# DDS_channel.net
KiCad netlist of a schematic drawn in Altium Designer
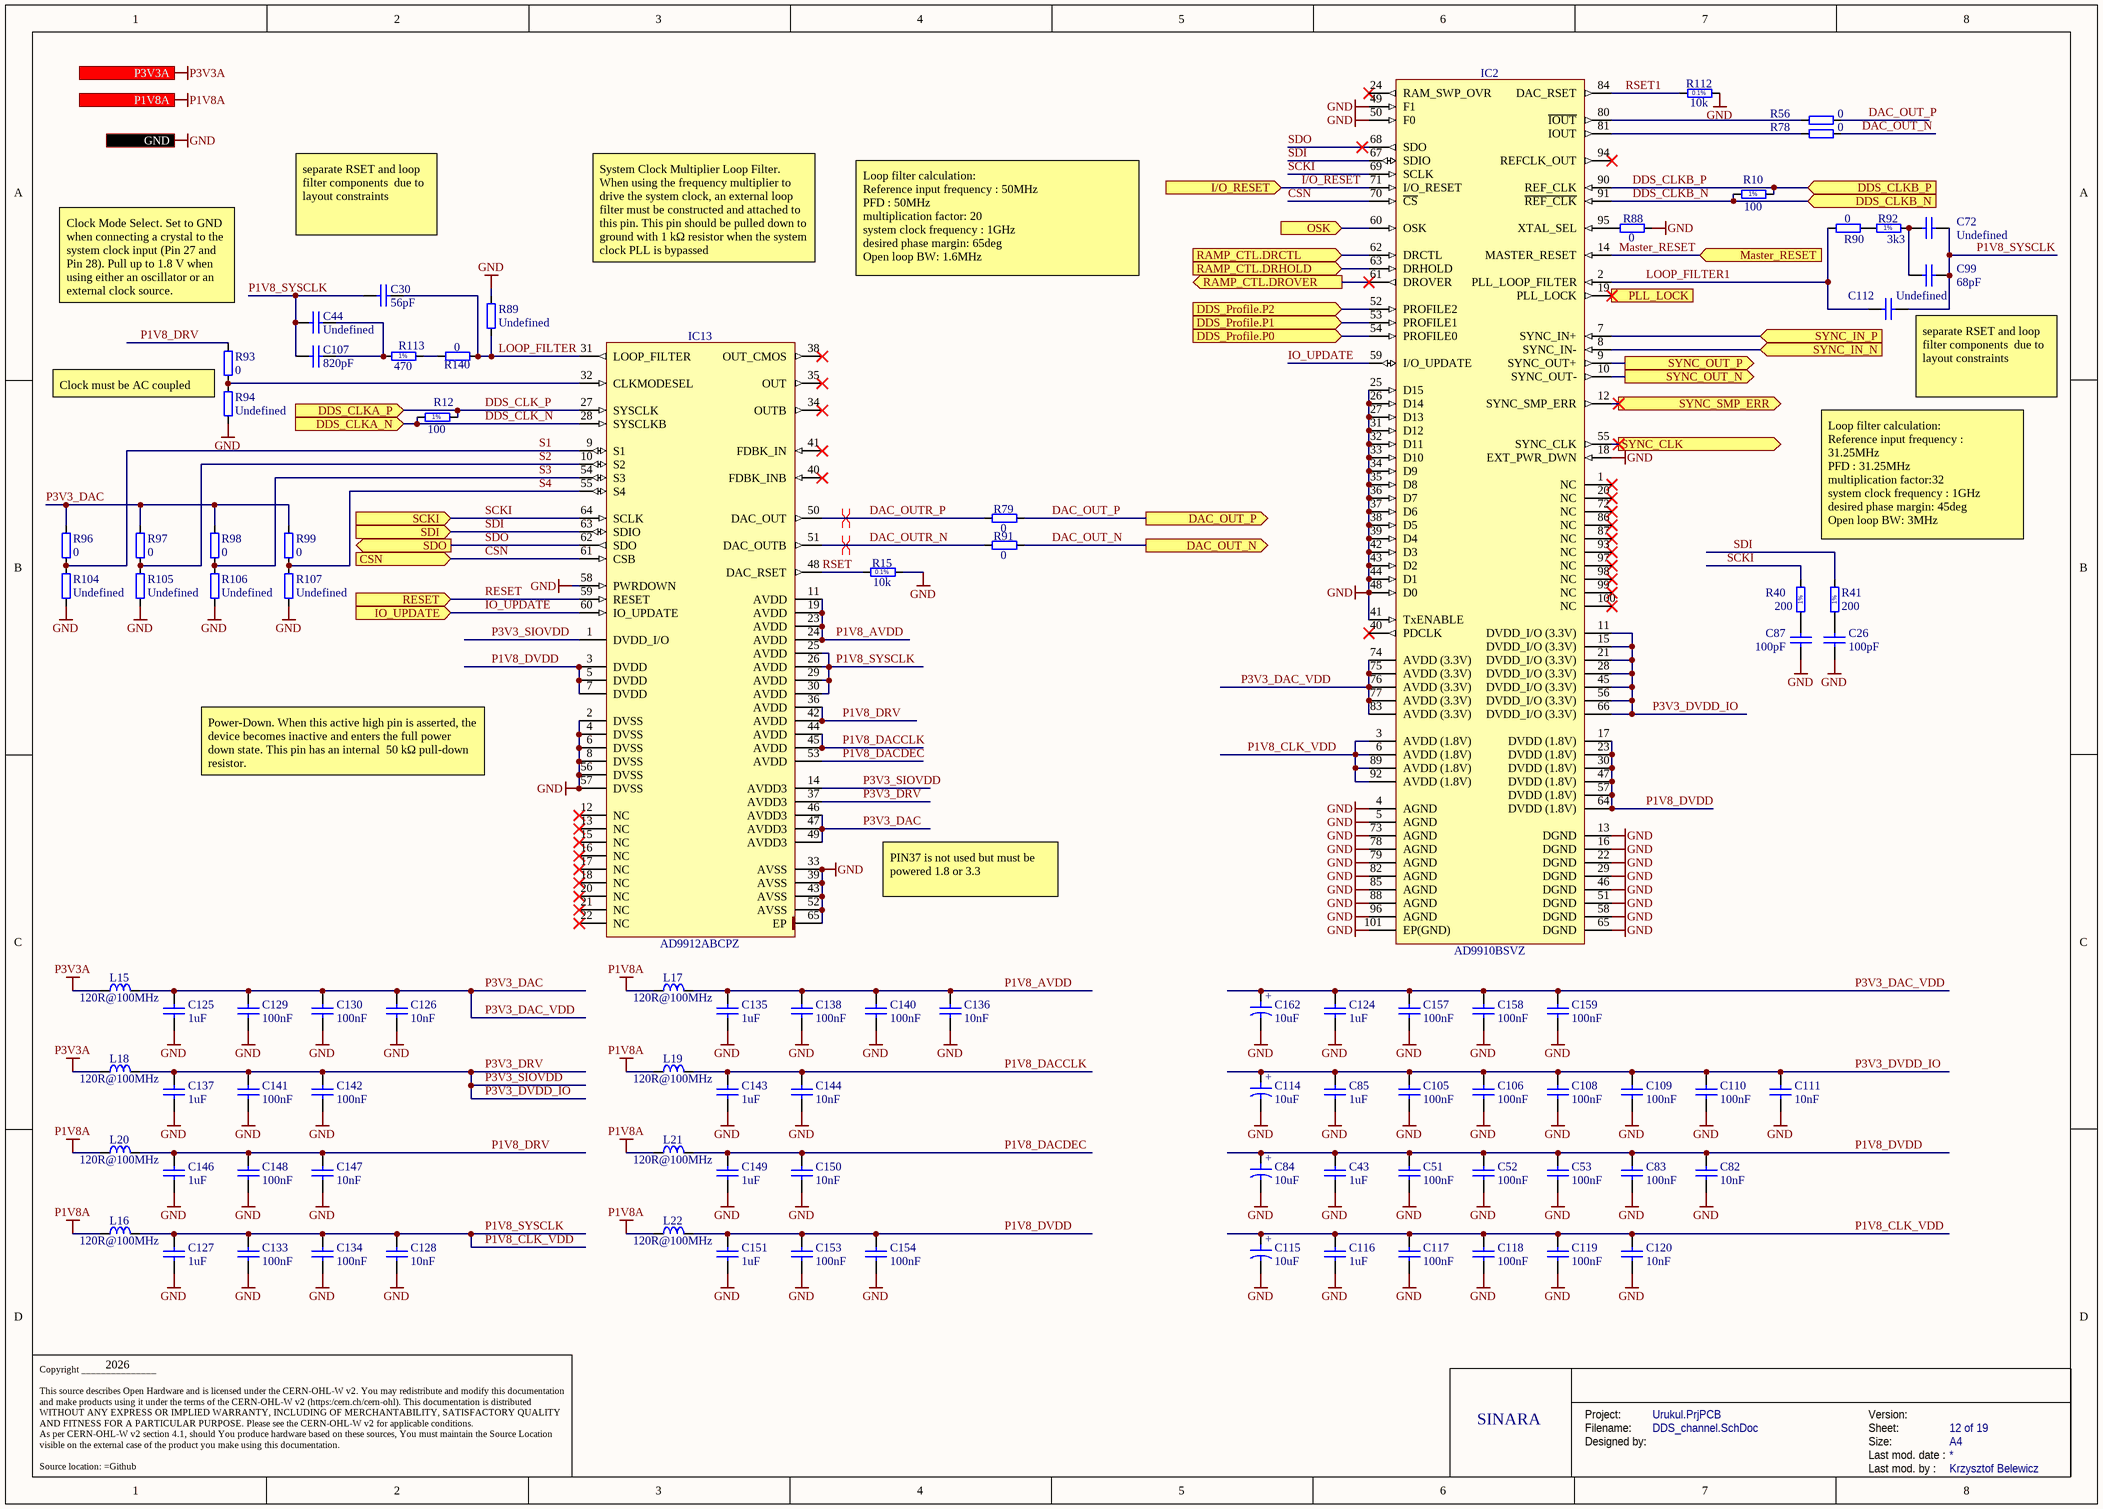
[diagram p0: DDS_channel.SchDoc]

(export (version "E")
  (design (tool "Eeschema 10.0.6"))
  (components
    (comp (ref "C26")
      (value "100pF")
      (footprint "CAPC1005X55N")
      (description "Non-polarised capacitor")
      (fields
        (field (name "PART NUMBER") "CC0402_100PF_50V_5%_C0G")
        (field (name "VOLTAGE") "50V")
        (field (name "AUTHOR") "CERN DEM JLC")
      )
      (libsource (lib "Capacitors") (part "Capacitor - non polarized"))
    )
    (comp (ref "C30")
      (value "56pF")
      (footprint "CAPC1608X87N")
      (description "Non-polarised capacitor")
      (fields
        (field (name "PART NUMBER") "CC0603_56PF_50V_5%_NP0")
        (field (name "VOLTAGE") "50V")
        (field (name "AUTHOR") "CERN DEM JLC")
      )
      (libsource (lib "Capacitors") (part "Capacitor - non polarized"))
    )
    (comp (ref "C43")
      (value "1uF")
      (footprint "CAPC1005X55N")
      (description "Non-polarised capacitor")
      (fields
        (field (name "PART NUMBER") "CC0402_1UF_16V_10%_X5R")
        (field (name "VOLTAGE") "16V")
        (field (name "AUTHOR") "CERN DEM JLC")
      )
      (libsource (lib "Capacitors") (part "Capacitor - non polarized"))
    )
    (comp (ref "C44")
      (value "Undefined")
      (footprint "CAPC1608X90N")
      (description "Non-polarised capacitor")
      (fields (field (name "PART NUMBER") "CC0603_NO-VALUE") (field (name "AUTHOR") "CERN DEM MR"))
      (libsource (lib "Capacitors") (part "Capacitor - non polarized"))
    )
    (comp (ref "C51")
      (value "100nF")
      (footprint "CAPC1005X55N")
      (description "Non-polarised capacitor")
      (fields
        (field (name "PART NUMBER") "CC0402_100NF_16V_10%_X5R")
        (field (name "VOLTAGE") "16V")
        (field (name "AUTHOR") "CERN DEM JLC")
      )
      (libsource (lib "Capacitors") (part "Capacitor - non polarized"))
    )
    (comp (ref "C52")
      (value "100nF")
      (footprint "CAPC1005X55N")
      (description "Non-polarised capacitor")
      (fields
        (field (name "PART NUMBER") "CC0402_100NF_16V_10%_X5R")
        (field (name "VOLTAGE") "16V")
        (field (name "AUTHOR") "CERN DEM JLC")
      )
      (libsource (lib "Capacitors") (part "Capacitor - non polarized"))
    )
    (comp (ref "C53")
      (value "100nF")
      (footprint "CAPC1005X55N")
      (description "Non-polarised capacitor")
      (fields
        (field (name "PART NUMBER") "CC0402_100NF_16V_10%_X5R")
        (field (name "VOLTAGE") "16V")
        (field (name "AUTHOR") "CERN DEM JLC")
      )
      (libsource (lib "Capacitors") (part "Capacitor - non polarized"))
    )
    (comp (ref "C72")
      (value "Undefined")
      (footprint "CAPC1608X90N")
      (description "Non-polarised capacitor")
      (fields (field (name "PART NUMBER") "CC0603_NO-VALUE") (field (name "AUTHOR") "CERN DEM MR"))
      (libsource (lib "Capacitors") (part "Capacitor - non polarized"))
    )
    (comp (ref "C82")
      (value "10nF")
      (footprint "CAPC1005X55N")
      (description "Non-polarised capacitor")
      (fields
        (field (name "PART NUMBER") "CC0402_10NF_16V_10%_X7R")
        (field (name "VOLTAGE") "16V")
        (field (name "AUTHOR") "CERN DEM JLC")
      )
      (libsource (lib "Capacitors") (part "Capacitor - non polarized"))
    )
    (comp (ref "C83")
      (value "100nF")
      (footprint "CAPC1005X55N")
      (description "Non-polarised capacitor")
      (fields
        (field (name "PART NUMBER") "CC0402_100NF_16V_10%_X5R")
        (field (name "VOLTAGE") "16V")
        (field (name "AUTHOR") "CERN DEM JLC")
      )
      (libsource (lib "Capacitors") (part "Capacitor - non polarized"))
    )
    (comp (ref "C84")
      (value "10uF")
      (footprint "CAPMP6032X280N")
      (description "Polarised capacitor")
      (fields
        (field (name "PART NUMBER") "CTE6032-28_10UF_25V_10%_LESR0500")
        (field (name "VOLTAGE") "25V")
        (field (name "AUTHOR") "CERN DEM JLC")
      )
      (libsource (lib "Capacitors") (part "Capacitor - polarized"))
    )
    (comp (ref "C85")
      (value "1uF")
      (footprint "CAPC1005X55N")
      (description "Non-polarised capacitor")
      (fields
        (field (name "PART NUMBER") "CC0402_1UF_16V_10%_X5R")
        (field (name "VOLTAGE") "16V")
        (field (name "AUTHOR") "CERN DEM JLC")
      )
      (libsource (lib "Capacitors") (part "Capacitor - non polarized"))
    )
    (comp (ref "C87")
      (value "100pF")
      (footprint "CAPC1005X55N")
      (description "Non-polarised capacitor")
      (fields
        (field (name "PART NUMBER") "CC0402_100PF_50V_5%_C0G")
        (field (name "VOLTAGE") "50V")
        (field (name "AUTHOR") "CERN DEM JLC")
      )
      (libsource (lib "Capacitors") (part "Capacitor - non polarized"))
    )
    (comp (ref "C99")
      (value "68pF")
      (footprint "CAPC1608X87N")
      (description "Non-polarised capacitor")
      (fields
        (field (name "PART NUMBER") "CC0603_68PF_50V_5%_NP0")
        (field (name "VOLTAGE") "50V")
        (field (name "AUTHOR") "CERN DEM JLC")
      )
      (libsource (lib "Capacitors") (part "Capacitor - non polarized"))
    )
    (comp (ref "C105")
      (value "100nF")
      (footprint "CAPC1005X55N")
      (description "Non-polarised capacitor")
      (fields
        (field (name "PART NUMBER") "CC0402_100NF_16V_10%_X5R")
        (field (name "VOLTAGE") "16V")
        (field (name "AUTHOR") "CERN DEM JLC")
      )
      (libsource (lib "Capacitors") (part "Capacitor - non polarized"))
    )
    (comp (ref "C106")
      (value "100nF")
      (footprint "CAPC1005X55N")
      (description "Non-polarised capacitor")
      (fields
        (field (name "PART NUMBER") "CC0402_100NF_16V_10%_X5R")
        (field (name "VOLTAGE") "16V")
        (field (name "AUTHOR") "CERN DEM JLC")
      )
      (libsource (lib "Capacitors") (part "Capacitor - non polarized"))
    )
    (comp (ref "C107")
      (value "820pF")
      (footprint "CAPC2012X135N")
      (description "Non-polarised capacitor")
      (fields
        (field (name "PART NUMBER") "CC0805_820PF_50V_5%_NP0")
        (field (name "VOLTAGE") "50V")
        (field (name "AUTHOR") "CERN DEM JLC")
      )
      (libsource (lib "Capacitors") (part "Capacitor - non polarized"))
    )
    (comp (ref "C108")
      (value "100nF")
      (footprint "CAPC1005X55N")
      (description "Non-polarised capacitor")
      (fields
        (field (name "PART NUMBER") "CC0402_100NF_16V_10%_X5R")
        (field (name "VOLTAGE") "16V")
        (field (name "AUTHOR") "CERN DEM JLC")
      )
      (libsource (lib "Capacitors") (part "Capacitor - non polarized"))
    )
    (comp (ref "C109")
      (value "100nF")
      (footprint "CAPC1005X55N")
      (description "Non-polarised capacitor")
      (fields
        (field (name "PART NUMBER") "CC0402_100NF_16V_10%_X5R")
        (field (name "VOLTAGE") "16V")
        (field (name "AUTHOR") "CERN DEM JLC")
      )
      (libsource (lib "Capacitors") (part "Capacitor - non polarized"))
    )
    (comp (ref "C110")
      (value "100nF")
      (footprint "CAPC1005X55N")
      (description "Non-polarised capacitor")
      (fields
        (field (name "PART NUMBER") "CC0402_100NF_16V_10%_X5R")
        (field (name "VOLTAGE") "16V")
        (field (name "AUTHOR") "CERN DEM JLC")
      )
      (libsource (lib "Capacitors") (part "Capacitor - non polarized"))
    )
    (comp (ref "C111")
      (value "10nF")
      (footprint "CAPC1005X55N")
      (description "Non-polarised capacitor")
      (fields
        (field (name "PART NUMBER") "CC0402_10NF_16V_10%_X7R")
        (field (name "VOLTAGE") "16V")
        (field (name "AUTHOR") "CERN DEM JLC")
      )
      (libsource (lib "Capacitors") (part "Capacitor - non polarized"))
    )
    (comp (ref "C112")
      (value "Undefined")
      (footprint "CAPC1608X90N")
      (description "Non-polarised capacitor")
      (fields (field (name "PART NUMBER") "CC0603_NO-VALUE") (field (name "AUTHOR") "CERN DEM MR"))
      (libsource (lib "Capacitors") (part "Capacitor - non polarized"))
    )
    (comp (ref "C114")
      (value "10uF")
      (footprint "CAPMP6032X280N")
      (description "Polarised capacitor")
      (fields
        (field (name "PART NUMBER") "CTE6032-28_10UF_25V_10%_LESR0500")
        (field (name "VOLTAGE") "25V")
        (field (name "AUTHOR") "CERN DEM JLC")
      )
      (libsource (lib "Capacitors") (part "Capacitor - polarized"))
    )
    (comp (ref "C115")
      (value "10uF")
      (footprint "CAPMP6032X280N")
      (description "Polarised capacitor")
      (fields
        (field (name "PART NUMBER") "CTE6032-28_10UF_25V_10%_LESR0500")
        (field (name "VOLTAGE") "25V")
        (field (name "AUTHOR") "CERN DEM JLC")
      )
      (libsource (lib "Capacitors") (part "Capacitor - polarized"))
    )
    (comp (ref "C116")
      (value "1uF")
      (footprint "CAPC1005X55N")
      (description "Non-polarised capacitor")
      (fields
        (field (name "PART NUMBER") "CC0402_1UF_16V_10%_X5R")
        (field (name "VOLTAGE") "16V")
        (field (name "AUTHOR") "CERN DEM JLC")
      )
      (libsource (lib "Capacitors") (part "Capacitor - non polarized"))
    )
    (comp (ref "C117")
      (value "100nF")
      (footprint "CAPC1005X55N")
      (description "Non-polarised capacitor")
      (fields
        (field (name "PART NUMBER") "CC0402_100NF_16V_10%_X5R")
        (field (name "VOLTAGE") "16V")
        (field (name "AUTHOR") "CERN DEM JLC")
      )
      (libsource (lib "Capacitors") (part "Capacitor - non polarized"))
    )
    (comp (ref "C118")
      (value "100nF")
      (footprint "CAPC1005X55N")
      (description "Non-polarised capacitor")
      (fields
        (field (name "PART NUMBER") "CC0402_100NF_16V_10%_X5R")
        (field (name "VOLTAGE") "16V")
        (field (name "AUTHOR") "CERN DEM JLC")
      )
      (libsource (lib "Capacitors") (part "Capacitor - non polarized"))
    )
    (comp (ref "C119")
      (value "100nF")
      (footprint "CAPC1005X55N")
      (description "Non-polarised capacitor")
      (fields
        (field (name "PART NUMBER") "CC0402_100NF_16V_10%_X5R")
        (field (name "VOLTAGE") "16V")
        (field (name "AUTHOR") "CERN DEM JLC")
      )
      (libsource (lib "Capacitors") (part "Capacitor - non polarized"))
    )
    (comp (ref "C120")
      (value "10nF")
      (footprint "CAPC1005X55N")
      (description "Non-polarised capacitor")
      (fields
        (field (name "PART NUMBER") "CC0402_10NF_16V_10%_X7R")
        (field (name "VOLTAGE") "16V")
        (field (name "AUTHOR") "CERN DEM JLC")
      )
      (libsource (lib "Capacitors") (part "Capacitor - non polarized"))
    )
    (comp (ref "C124")
      (value "1uF")
      (footprint "CAPC1005X55N")
      (description "Non-polarised capacitor")
      (fields
        (field (name "PART NUMBER") "CC0402_1UF_16V_10%_X5R")
        (field (name "VOLTAGE") "16V")
        (field (name "AUTHOR") "CERN DEM JLC")
      )
      (libsource (lib "Capacitors") (part "Capacitor - non polarized"))
    )
    (comp (ref "C125")
      (value "1uF")
      (footprint "CAPC1005X55N")
      (description "Non-polarised capacitor")
      (fields
        (field (name "PART NUMBER") "CC0402_1UF_16V_10%_X5R")
        (field (name "VOLTAGE") "16V")
        (field (name "AUTHOR") "CERN DEM JLC")
      )
      (libsource (lib "Capacitors") (part "Capacitor - non polarized"))
    )
    (comp (ref "C126")
      (value "10nF")
      (footprint "CAPC1005X55N")
      (description "Non-polarised capacitor")
      (fields
        (field (name "PART NUMBER") "CC0402_10NF_16V_10%_X7R")
        (field (name "VOLTAGE") "16V")
        (field (name "AUTHOR") "CERN DEM JLC")
      )
      (libsource (lib "Capacitors") (part "Capacitor - non polarized"))
    )
    (comp (ref "C127")
      (value "1uF")
      (footprint "CAPC1005X55N")
      (description "Non-polarised capacitor")
      (fields
        (field (name "PART NUMBER") "CC0402_1UF_16V_10%_X5R")
        (field (name "VOLTAGE") "16V")
        (field (name "AUTHOR") "CERN DEM JLC")
      )
      (libsource (lib "Capacitors") (part "Capacitor - non polarized"))
    )
    (comp (ref "C128")
      (value "10nF")
      (footprint "CAPC1005X55N")
      (description "Non-polarised capacitor")
      (fields
        (field (name "PART NUMBER") "CC0402_10NF_16V_10%_X7R")
        (field (name "VOLTAGE") "16V")
        (field (name "AUTHOR") "CERN DEM JLC")
      )
      (libsource (lib "Capacitors") (part "Capacitor - non polarized"))
    )
    (comp (ref "C129")
      (value "100nF")
      (footprint "CAPC1005X55N")
      (description "Non-polarised capacitor")
      (fields
        (field (name "PART NUMBER") "CC0402_100NF_16V_10%_X5R")
        (field (name "VOLTAGE") "16V")
        (field (name "AUTHOR") "CERN DEM JLC")
      )
      (libsource (lib "Capacitors") (part "Capacitor - non polarized"))
    )
    (comp (ref "C130")
      (value "100nF")
      (footprint "CAPC1005X55N")
      (description "Non-polarised capacitor")
      (fields
        (field (name "PART NUMBER") "CC0402_100NF_16V_10%_X5R")
        (field (name "VOLTAGE") "16V")
        (field (name "AUTHOR") "CERN DEM JLC")
      )
      (libsource (lib "Capacitors") (part "Capacitor - non polarized"))
    )
    (comp (ref "C133")
      (value "100nF")
      (footprint "CAPC1005X55N")
      (description "Non-polarised capacitor")
      (fields
        (field (name "PART NUMBER") "CC0402_100NF_16V_10%_X5R")
        (field (name "VOLTAGE") "16V")
        (field (name "AUTHOR") "CERN DEM JLC")
      )
      (libsource (lib "Capacitors") (part "Capacitor - non polarized"))
    )
    (comp (ref "C134")
      (value "100nF")
      (footprint "CAPC1005X55N")
      (description "Non-polarised capacitor")
      (fields
        (field (name "PART NUMBER") "CC0402_100NF_16V_10%_X5R")
        (field (name "VOLTAGE") "16V")
        (field (name "AUTHOR") "CERN DEM JLC")
      )
      (libsource (lib "Capacitors") (part "Capacitor - non polarized"))
    )
    (comp (ref "C135")
      (value "1uF")
      (footprint "CAPC1005X55N")
      (description "Non-polarised capacitor")
      (fields
        (field (name "PART NUMBER") "CC0402_1UF_16V_10%_X5R")
        (field (name "VOLTAGE") "16V")
        (field (name "AUTHOR") "CERN DEM JLC")
      )
      (libsource (lib "Capacitors") (part "Capacitor - non polarized"))
    )
    (comp (ref "C136")
      (value "10nF")
      (footprint "CAPC1005X55N")
      (description "Non-polarised capacitor")
      (fields
        (field (name "PART NUMBER") "CC0402_10NF_16V_10%_X7R")
        (field (name "VOLTAGE") "16V")
        (field (name "AUTHOR") "CERN DEM JLC")
      )
      (libsource (lib "Capacitors") (part "Capacitor - non polarized"))
    )
    (comp (ref "C137")
      (value "1uF")
      (footprint "CAPC1005X55N")
      (description "Non-polarised capacitor")
      (fields
        (field (name "PART NUMBER") "CC0402_1UF_16V_10%_X5R")
        (field (name "VOLTAGE") "16V")
        (field (name "AUTHOR") "CERN DEM JLC")
      )
      (libsource (lib "Capacitors") (part "Capacitor - non polarized"))
    )
    (comp (ref "C138")
      (value "100nF")
      (footprint "CAPC1005X55N")
      (description "Non-polarised capacitor")
      (fields
        (field (name "PART NUMBER") "CC0402_100NF_16V_10%_X5R")
        (field (name "VOLTAGE") "16V")
        (field (name "AUTHOR") "CERN DEM JLC")
      )
      (libsource (lib "Capacitors") (part "Capacitor - non polarized"))
    )
    (comp (ref "C140")
      (value "100nF")
      (footprint "CAPC1005X55N")
      (description "Non-polarised capacitor")
      (fields
        (field (name "PART NUMBER") "CC0402_100NF_16V_10%_X5R")
        (field (name "VOLTAGE") "16V")
        (field (name "AUTHOR") "CERN DEM JLC")
      )
      (libsource (lib "Capacitors") (part "Capacitor - non polarized"))
    )
    (comp (ref "C141")
      (value "100nF")
      (footprint "CAPC1005X55N")
      (description "Non-polarised capacitor")
      (fields
        (field (name "PART NUMBER") "CC0402_100NF_16V_10%_X5R")
        (field (name "VOLTAGE") "16V")
        (field (name "AUTHOR") "CERN DEM JLC")
      )
      (libsource (lib "Capacitors") (part "Capacitor - non polarized"))
    )
    (comp (ref "C142")
      (value "100nF")
      (footprint "CAPC1005X55N")
      (description "Non-polarised capacitor")
      (fields
        (field (name "PART NUMBER") "CC0402_100NF_16V_10%_X5R")
        (field (name "VOLTAGE") "16V")
        (field (name "AUTHOR") "CERN DEM JLC")
      )
      (libsource (lib "Capacitors") (part "Capacitor - non polarized"))
    )
    (comp (ref "C143")
      (value "1uF")
      (footprint "CAPC1005X55N")
      (description "Non-polarised capacitor")
      (fields
        (field (name "PART NUMBER") "CC0402_1UF_16V_10%_X5R")
        (field (name "VOLTAGE") "16V")
        (field (name "AUTHOR") "CERN DEM JLC")
      )
      (libsource (lib "Capacitors") (part "Capacitor - non polarized"))
    )
    (comp (ref "C144")
      (value "10nF")
      (footprint "CAPC1005X55N")
      (description "Non-polarised capacitor")
      (fields
        (field (name "PART NUMBER") "CC0402_10NF_16V_10%_X7R")
        (field (name "VOLTAGE") "16V")
        (field (name "AUTHOR") "CERN DEM JLC")
      )
      (libsource (lib "Capacitors") (part "Capacitor - non polarized"))
    )
    (comp (ref "C146")
      (value "1uF")
      (footprint "CAPC1005X55N")
      (description "Non-polarised capacitor")
      (fields
        (field (name "PART NUMBER") "CC0402_1UF_16V_10%_X5R")
        (field (name "VOLTAGE") "16V")
        (field (name "AUTHOR") "CERN DEM JLC")
      )
      (libsource (lib "Capacitors") (part "Capacitor - non polarized"))
    )
    (comp (ref "C147")
      (value "10nF")
      (footprint "CAPC1005X55N")
      (description "Non-polarised capacitor")
      (fields
        (field (name "PART NUMBER") "CC0402_10NF_16V_10%_X7R")
        (field (name "VOLTAGE") "16V")
        (field (name "AUTHOR") "CERN DEM JLC")
      )
      (libsource (lib "Capacitors") (part "Capacitor - non polarized"))
    )
    (comp (ref "C148")
      (value "100nF")
      (footprint "CAPC1005X55N")
      (description "Non-polarised capacitor")
      (fields
        (field (name "PART NUMBER") "CC0402_100NF_16V_10%_X5R")
        (field (name "VOLTAGE") "16V")
        (field (name "AUTHOR") "CERN DEM JLC")
      )
      (libsource (lib "Capacitors") (part "Capacitor - non polarized"))
    )
    (comp (ref "C149")
      (value "1uF")
      (footprint "CAPC1005X55N")
      (description "Non-polarised capacitor")
      (fields
        (field (name "PART NUMBER") "CC0402_1UF_16V_10%_X5R")
        (field (name "VOLTAGE") "16V")
        (field (name "AUTHOR") "CERN DEM JLC")
      )
      (libsource (lib "Capacitors") (part "Capacitor - non polarized"))
    )
    (comp (ref "C150")
      (value "10nF")
      (footprint "CAPC1005X55N")
      (description "Non-polarised capacitor")
      (fields
        (field (name "PART NUMBER") "CC0402_10NF_16V_10%_X7R")
        (field (name "VOLTAGE") "16V")
        (field (name "AUTHOR") "CERN DEM JLC")
      )
      (libsource (lib "Capacitors") (part "Capacitor - non polarized"))
    )
    (comp (ref "C151")
      (value "1uF")
      (footprint "CAPC1005X55N")
      (description "Non-polarised capacitor")
      (fields
        (field (name "PART NUMBER") "CC0402_1UF_16V_10%_X5R")
        (field (name "VOLTAGE") "16V")
        (field (name "AUTHOR") "CERN DEM JLC")
      )
      (libsource (lib "Capacitors") (part "Capacitor - non polarized"))
    )
    (comp (ref "C153")
      (value "100nF")
      (footprint "CAPC1005X55N")
      (description "Non-polarised capacitor")
      (fields
        (field (name "PART NUMBER") "CC0402_100NF_16V_10%_X5R")
        (field (name "VOLTAGE") "16V")
        (field (name "AUTHOR") "CERN DEM JLC")
      )
      (libsource (lib "Capacitors") (part "Capacitor - non polarized"))
    )
    (comp (ref "C154")
      (value "100nF")
      (footprint "CAPC1005X55N")
      (description "Non-polarised capacitor")
      (fields
        (field (name "PART NUMBER") "CC0402_100NF_16V_10%_X5R")
        (field (name "VOLTAGE") "16V")
        (field (name "AUTHOR") "CERN DEM JLC")
      )
      (libsource (lib "Capacitors") (part "Capacitor - non polarized"))
    )
    (comp (ref "C157")
      (value "100nF")
      (footprint "CAPC1005X55N")
      (description "Non-polarised capacitor")
      (fields
        (field (name "PART NUMBER") "CC0402_100NF_16V_10%_X5R")
        (field (name "VOLTAGE") "16V")
        (field (name "AUTHOR") "CERN DEM JLC")
      )
      (libsource (lib "Capacitors") (part "Capacitor - non polarized"))
    )
    (comp (ref "C158")
      (value "100nF")
      (footprint "CAPC1005X55N")
      (description "Non-polarised capacitor")
      (fields
        (field (name "PART NUMBER") "CC0402_100NF_16V_10%_X5R")
        (field (name "VOLTAGE") "16V")
        (field (name "AUTHOR") "CERN DEM JLC")
      )
      (libsource (lib "Capacitors") (part "Capacitor - non polarized"))
    )
    (comp (ref "C159")
      (value "100nF")
      (footprint "CAPC1005X55N")
      (description "Non-polarised capacitor")
      (fields
        (field (name "PART NUMBER") "CC0402_100NF_16V_10%_X5R")
        (field (name "VOLTAGE") "16V")
        (field (name "AUTHOR") "CERN DEM JLC")
      )
      (libsource (lib "Capacitors") (part "Capacitor - non polarized"))
    )
    (comp (ref "C162")
      (value "10uF")
      (footprint "CAPMP6032X280N")
      (description "Polarised capacitor")
      (fields
        (field (name "PART NUMBER") "CTE6032-28_10UF_25V_10%_LESR0500")
        (field (name "VOLTAGE") "25V")
        (field (name "AUTHOR") "CERN DEM JLC")
      )
      (libsource (lib "Capacitors") (part "Capacitor - polarized"))
    )
    (comp (ref "IC2")
      (value "AD9910BSVZ")
      (footprint "QFP50P1600X1600X120-101N-S500")
      (description "1 GSPS, 14-Bit, 3.3 V CMOS Direct Digital Synthesizer")
      (fields (field (name "MANUFACTURER") "ANALOG DEVICES") (field (name "AUTHOR") "CERN DEM JLC"))
      (libsource (lib "ICs And Semiconductors") (part "AD9910"))
    )
    (comp (ref "IC13")
      (value "AD9912ABCPZ")
      (footprint "QFN50P900X900X100-65N-S536")
      (description "1 GSPS Direct Digital Synthetizer with 14-Bit DAC")
      (fields (field (name "MANUFACTURER") "ANALOG DEVICES") (field (name "AUTHOR") "CERN DEM JLC"))
      (libsource (lib "ICs And Semiconductors") (part "AD9912"))
    )
    (comp (ref "L15")
      (value "120R@100MHz")
      (footprint "INDC1608X95N")
      (description "Inductor")
      (fields
        (field (name "PART NUMBER") "IND0603_MURATA_BLM18PG121SN1D")
        (field (name "POWER") "2A")
        (field (name "AUTHOR") "CERN DEM BC")
      )
      (libsource (lib "Inductors & Transformers") (part "Inductor"))
    )
    (comp (ref "L16")
      (value "120R@100MHz")
      (footprint "INDC1608X95N")
      (description "Inductor")
      (fields
        (field (name "PART NUMBER") "IND0603_MURATA_BLM18PG121SN1D")
        (field (name "POWER") "2A")
        (field (name "AUTHOR") "CERN DEM BC")
      )
      (libsource (lib "Inductors & Transformers") (part "Inductor"))
    )
    (comp (ref "L17")
      (value "120R@100MHz")
      (footprint "INDC1608X95N")
      (description "Inductor")
      (fields
        (field (name "PART NUMBER") "IND0603_MURATA_BLM18PG121SN1D")
        (field (name "POWER") "2A")
        (field (name "AUTHOR") "CERN DEM BC")
      )
      (libsource (lib "Inductors & Transformers") (part "Inductor"))
    )
    (comp (ref "L18")
      (value "120R@100MHz")
      (footprint "INDC1608X95N")
      (description "Inductor")
      (fields
        (field (name "PART NUMBER") "IND0603_MURATA_BLM18PG121SN1D")
        (field (name "POWER") "2A")
        (field (name "AUTHOR") "CERN DEM BC")
      )
      (libsource (lib "Inductors & Transformers") (part "Inductor"))
    )
    (comp (ref "L19")
      (value "120R@100MHz")
      (footprint "INDC1608X95N")
      (description "Inductor")
      (fields
        (field (name "PART NUMBER") "IND0603_MURATA_BLM18PG121SN1D")
        (field (name "POWER") "2A")
        (field (name "AUTHOR") "CERN DEM BC")
      )
      (libsource (lib "Inductors & Transformers") (part "Inductor"))
    )
    (comp (ref "L20")
      (value "120R@100MHz")
      (footprint "INDC1608X95N")
      (description "Inductor")
      (fields
        (field (name "PART NUMBER") "IND0603_MURATA_BLM18PG121SN1D")
        (field (name "POWER") "2A")
        (field (name "AUTHOR") "CERN DEM BC")
      )
      (libsource (lib "Inductors & Transformers") (part "Inductor"))
    )
    (comp (ref "L21")
      (value "120R@100MHz")
      (footprint "INDC1608X95N")
      (description "Inductor")
      (fields
        (field (name "PART NUMBER") "IND0603_MURATA_BLM18PG121SN1D")
        (field (name "POWER") "2A")
        (field (name "AUTHOR") "CERN DEM BC")
      )
      (libsource (lib "Inductors & Transformers") (part "Inductor"))
    )
    (comp (ref "L22")
      (value "120R@100MHz")
      (footprint "INDC1608X95N")
      (description "Inductor")
      (fields
        (field (name "PART NUMBER") "IND0603_MURATA_BLM18PG121SN1D")
        (field (name "POWER") "2A")
        (field (name "AUTHOR") "CERN DEM BC")
      )
      (libsource (lib "Inductors & Transformers") (part "Inductor"))
    )
    (comp (ref "R10")
      (value "100")
      (footprint "RESC1005X40N")
      (description "Resistor - 1%")
      (fields
        (field (name "PART NUMBER") "R0402_100R_1%_0.0625W_100PPM")
        (field (name "POWER") "0.0625W")
        (field (name "AUTHOR") "CERN DEM JLC")
      )
      (libsource (lib "Resistors") (part "Resistor - 1%"))
    )
    (comp (ref "R12")
      (value "100")
      (footprint "RESC1005X40N")
      (description "Resistor - 1%")
      (fields
        (field (name "PART NUMBER") "R0402_100R_1%_0.0625W_100PPM")
        (field (name "POWER") "0.0625W")
        (field (name "AUTHOR") "CERN DEM JLC")
      )
      (libsource (lib "Resistors") (part "Resistor - 1%"))
    )
    (comp (ref "R15")
      (value "10k")
      (footprint "RESC1005X35N")
      (description "Resistor - 0.1%")
      (fields
        (field (name "PART NUMBER") "R0402_10K_0.1%_0.063W_25PPM")
        (field (name "POWER") "0.063W")
        (field (name "AUTHOR") "CERN DEM JMW")
      )
      (libsource (lib "Resistors") (part "Resistor - 0.1%"))
    )
    (comp (ref "R40")
      (value "200")
      (footprint "RESC1005X40N")
      (description "Resistor - 1%")
      (fields
        (field (name "PART NUMBER") "R0402_200R_1%_0.0625W_100PPM")
        (field (name "POWER") "0.0625W")
        (field (name "AUTHOR") "CERN DEM JLC")
      )
      (libsource (lib "Resistors") (part "Resistor - 1%"))
    )
    (comp (ref "R41")
      (value "200")
      (footprint "RESC1005X40N")
      (description "Resistor - 1%")
      (fields
        (field (name "PART NUMBER") "R0402_200R_1%_0.0625W_100PPM")
        (field (name "POWER") "0.0625W")
        (field (name "AUTHOR") "CERN DEM JLC")
      )
      (libsource (lib "Resistors") (part "Resistor - 1%"))
    )
    (comp (ref "R56")
      (value "0")
      (footprint "RESC1005X40N")
      (description "Resistor")
      (fields
        (field (name "PART NUMBER") "R0402_0R_JUMPER")
        (field (name "MANUFACTURER") "GENERIC")
        (field (name "AUTHOR") "CERN DEM JLC")
      )
      (libsource (lib "Resistors") (part "Resistor"))
    )
    (comp (ref "R78")
      (value "0")
      (footprint "RESC1005X40N")
      (description "Resistor")
      (fields
        (field (name "PART NUMBER") "R0402_0R_JUMPER")
        (field (name "MANUFACTURER") "GENERIC")
        (field (name "AUTHOR") "CERN DEM JLC")
      )
      (libsource (lib "Resistors") (part "Resistor"))
    )
    (comp (ref "R79")
      (value "0")
      (footprint "RESC1005X40N")
      (description "Resistor")
      (fields
        (field (name "PART NUMBER") "R0402_0R_JUMPER")
        (field (name "MANUFACTURER") "GENERIC")
        (field (name "AUTHOR") "CERN DEM JLC")
      )
      (libsource (lib "Resistors") (part "Resistor"))
    )
    (comp (ref "R88")
      (value "0")
      (footprint "RESC1005X40N")
      (description "Resistor")
      (fields
        (field (name "PART NUMBER") "R0402_0R_JUMPER")
        (field (name "MANUFACTURER") "GENERIC")
        (field (name "AUTHOR") "CERN DEM JLC")
      )
      (libsource (lib "Resistors") (part "Resistor"))
    )
    (comp (ref "R89")
      (value "Undefined")
      (footprint "RESC1005X40N")
      (description "Resistor")
      (fields (field (name "PART NUMBER") "R0402_NO-VALUE") (field (name "AUTHOR") "CERN DEM JLC"))
      (libsource (lib "Resistors") (part "Resistor"))
    )
    (comp (ref "R90")
      (value "0")
      (footprint "RESC1608X55N")
      (description "Resistor")
      (fields
        (field (name "PART NUMBER") "R0603_0R_JUMPER")
        (field (name "MANUFACTURER") "GENERIC")
        (field (name "AUTHOR") "CERN DEM JLC")
      )
      (libsource (lib "Resistors") (part "Resistor"))
    )
    (comp (ref "R91")
      (value "0")
      (footprint "RESC1005X40N")
      (description "Resistor")
      (fields
        (field (name "PART NUMBER") "R0402_0R_JUMPER")
        (field (name "MANUFACTURER") "GENERIC")
        (field (name "AUTHOR") "CERN DEM JLC")
      )
      (libsource (lib "Resistors") (part "Resistor"))
    )
    (comp (ref "R92")
      (value "3k3")
      (footprint "RESC1608X55N")
      (description "Resistor - 1%")
      (fields
        (field (name "PART NUMBER") "R0603_3K3_1%_0.1W_100PPM")
        (field (name "POWER") "0.1W")
        (field (name "AUTHOR") "CERN DEM JLC")
      )
      (libsource (lib "Resistors") (part "Resistor - 1%"))
    )
    (comp (ref "R93")
      (value "0")
      (footprint "RESC1005X40N")
      (description "Resistor")
      (fields
        (field (name "PART NUMBER") "R0402_0R_JUMPER")
        (field (name "MANUFACTURER") "GENERIC")
        (field (name "AUTHOR") "CERN DEM JLC")
      )
      (libsource (lib "Resistors") (part "Resistor"))
    )
    (comp (ref "R94")
      (value "Undefined")
      (footprint "RESC1005X40N")
      (description "Resistor")
      (fields (field (name "PART NUMBER") "R0402_NO-VALUE") (field (name "AUTHOR") "CERN DEM JLC"))
      (libsource (lib "Resistors") (part "Resistor"))
    )
    (comp (ref "R96")
      (value "0")
      (footprint "RESC1005X40N")
      (description "Resistor")
      (fields
        (field (name "PART NUMBER") "R0402_0R_JUMPER")
        (field (name "MANUFACTURER") "GENERIC")
        (field (name "AUTHOR") "CERN DEM JLC")
      )
      (libsource (lib "Resistors") (part "Resistor"))
    )
    (comp (ref "R97")
      (value "0")
      (footprint "RESC1005X40N")
      (description "Resistor")
      (fields
        (field (name "PART NUMBER") "R0402_0R_JUMPER")
        (field (name "MANUFACTURER") "GENERIC")
        (field (name "AUTHOR") "CERN DEM JLC")
      )
      (libsource (lib "Resistors") (part "Resistor"))
    )
    (comp (ref "R98")
      (value "0")
      (footprint "RESC1005X40N")
      (description "Resistor")
      (fields
        (field (name "PART NUMBER") "R0402_0R_JUMPER")
        (field (name "MANUFACTURER") "GENERIC")
        (field (name "AUTHOR") "CERN DEM JLC")
      )
      (libsource (lib "Resistors") (part "Resistor"))
    )
    (comp (ref "R99")
      (value "0")
      (footprint "RESC1005X40N")
      (description "Resistor")
      (fields
        (field (name "PART NUMBER") "R0402_0R_JUMPER")
        (field (name "MANUFACTURER") "GENERIC")
        (field (name "AUTHOR") "CERN DEM JLC")
      )
      (libsource (lib "Resistors") (part "Resistor"))
    )
    (comp (ref "R104")
      (value "Undefined")
      (footprint "RESC1005X40N")
      (description "Resistor")
      (fields (field (name "PART NUMBER") "R0402_NO-VALUE") (field (name "AUTHOR") "CERN DEM JLC"))
      (libsource (lib "Resistors") (part "Resistor"))
    )
    (comp (ref "R105")
      (value "Undefined")
      (footprint "RESC1005X40N")
      (description "Resistor")
      (fields (field (name "PART NUMBER") "R0402_NO-VALUE") (field (name "AUTHOR") "CERN DEM JLC"))
      (libsource (lib "Resistors") (part "Resistor"))
    )
    (comp (ref "R106")
      (value "Undefined")
      (footprint "RESC1005X40N")
      (description "Resistor")
      (fields (field (name "PART NUMBER") "R0402_NO-VALUE") (field (name "AUTHOR") "CERN DEM JLC"))
      (libsource (lib "Resistors") (part "Resistor"))
    )
    (comp (ref "R107")
      (value "Undefined")
      (footprint "RESC1005X40N")
      (description "Resistor")
      (fields (field (name "PART NUMBER") "R0402_NO-VALUE") (field (name "AUTHOR") "CERN DEM JLC"))
      (libsource (lib "Resistors") (part "Resistor"))
    )
    (comp (ref "R112")
      (value "10k")
      (footprint "RESC1005X35N")
      (description "Resistor - 0.1%")
      (fields
        (field (name "PART NUMBER") "R0402_10K_0.1%_0.063W_25PPM")
        (field (name "POWER") "0.063W")
        (field (name "AUTHOR") "CERN DEM JMW")
      )
      (libsource (lib "Resistors") (part "Resistor - 0.1%"))
    )
    (comp (ref "R113")
      (value "470")
      (footprint "RESC1608X55N")
      (description "Resistor - 1%")
      (fields
        (field (name "PART NUMBER") "R0603_470R_1%_0.1W_100PPM")
        (field (name "POWER") "0.1W")
        (field (name "AUTHOR") "CERN DEM JLC")
      )
      (libsource (lib "Resistors") (part "Resistor - 1%"))
    )
    (comp (ref "R140")
      (value "0")
      (footprint "RESC1608X55N")
      (description "Resistor")
      (fields
        (field (name "PART NUMBER") "R0603_0R_JUMPER")
        (field (name "MANUFACTURER") "GENERIC")
        (field (name "AUTHOR") "CERN DEM JLC")
      )
      (libsource (lib "Resistors") (part "Resistor"))
    )
  )
  (nets
    (net (code "1") (name "/CSN") (class "Default")
      (node (ref "IC13") (pin "61") (pinfunction "CSB_61") (pintype "input"))
      (node (ref "IC2") (pin "70") (pinfunction "CS_70") (pintype "input"))
    )
    (net (code "2") (name "/DAC_OUTR_N") (class "Default")
      (node (ref "IC13") (pin "51") (pinfunction "DAC_OUTB_51") (pintype "output"))
      (node (ref "R91") (pin "1") (pinfunction "1_1") (pintype "passive"))
    )
    (net (code "3") (name "/DAC_OUTR_P") (class "Default")
      (node (ref "IC13") (pin "50") (pinfunction "DAC_OUT_50") (pintype "output"))
      (node (ref "R79") (pin "1") (pinfunction "1_1") (pintype "passive"))
    )
    (net (code "4") (name "/DAC_OUT_N") (class "Default")
      (node (ref "R78") (pin "2") (pinfunction "2_2") (pintype "passive"))
      (node (ref "R91") (pin "2") (pinfunction "2_2") (pintype "passive"))
    )
    (net (code "5") (name "/DAC_OUT_P") (class "Default")
      (node (ref "R56") (pin "2") (pinfunction "2_2") (pintype "passive"))
      (node (ref "R79") (pin "2") (pinfunction "2_2") (pintype "passive"))
    )
    (net (code "6") (name "/DDS_CLKB_N") (class "Default")
      (node (ref "IC2") (pin "91") (pinfunction "REF_CLK_91") (pintype "input"))
      (node (ref "R10") (pin "2") (pinfunction "2_2") (pintype "passive"))
    )
    (net (code "7") (name "/DDS_CLKB_P") (class "Default")
      (node (ref "IC2") (pin "90") (pinfunction "REF_CLK_90") (pintype "input"))
      (node (ref "R10") (pin "1") (pinfunction "1_1") (pintype "passive"))
    )
    (net (code "8") (name "/DDS_CLK_N") (class "Default")
      (node (ref "IC13") (pin "28") (pinfunction "SYSCLKB_28") (pintype "input"))
      (node (ref "R12") (pin "2") (pinfunction "2_2") (pintype "passive"))
    )
    (net (code "9") (name "/DDS_CLK_P") (class "Default")
      (node (ref "IC13") (pin "27") (pinfunction "SYSCLK_27") (pintype "input"))
      (node (ref "R12") (pin "1") (pinfunction "1_1") (pintype "passive"))
    )
    (net (code "10") (name "/DDS_Profile.P0") (class "Default")
      (node (ref "IC2") (pin "54") (pinfunction "PROFILE0_54") (pintype "input"))
    )
    (net (code "11") (name "/DDS_Profile.P1") (class "Default")
      (node (ref "IC2") (pin "53") (pinfunction "PROFILE1_53") (pintype "input"))
    )
    (net (code "12") (name "/DDS_Profile.P2") (class "Default")
      (node (ref "IC2") (pin "52") (pinfunction "PROFILE2_52") (pintype "input"))
    )
    (net (code "13") (name "/IO_UPDATE") (class "Default")
      (node (ref "IC13") (pin "60") (pinfunction "IO_UPDATE_60") (pintype "input"))
      (node (ref "IC2") (pin "59") (pinfunction "I/O_UPDATE_59") (pintype "bidirectional"))
    )
    (net (code "14") (name "/I{slash}O_RESET") (class "Default")
      (node (ref "IC2") (pin "71") (pinfunction "I/O_RESET_71") (pintype "input"))
    )
    (net (code "15") (name "/LOOP_FILTER") (class "Default")
      (node (ref "C30") (pin "2") (pinfunction "2_2") (pintype "passive"))
      (node (ref "IC13") (pin "31") (pinfunction "LOOP_FILTER_31") (pintype "output"))
      (node (ref "R140") (pin "2") (pinfunction "2_2") (pintype "passive"))
      (node (ref "R89") (pin "1") (pinfunction "1_1") (pintype "passive"))
    )
    (net (code "16") (name "/LOOP_FILTER1") (class "Default")
      (node (ref "C112") (pin "2") (pinfunction "2_2") (pintype "passive"))
      (node (ref "IC2") (pin "2") (pinfunction "PLL_LOOP_FILTER_2") (pintype "input"))
      (node (ref "R90") (pin "2") (pinfunction "2_2") (pintype "passive"))
    )
    (net (code "17") (name "/Master_RESET") (class "Default")
      (node (ref "IC2") (pin "14") (pinfunction "MASTER_RESET_14") (pintype "input"))
    )
    (net (code "18") (name "/OSK") (class "Default")
      (node (ref "IC2") (pin "60") (pinfunction "OSK_60") (pintype "input"))
    )
    (net (code "19") (name "/P1V8_AVDD") (class "Default")
      (node (ref "C135") (pin "2") (pinfunction "2_2") (pintype "passive"))
      (node (ref "C136") (pin "2") (pinfunction "2_2") (pintype "passive"))
      (node (ref "C138") (pin "2") (pinfunction "2_2") (pintype "passive"))
      (node (ref "C140") (pin "2") (pinfunction "2_2") (pintype "passive"))
      (node (ref "IC13") (pin "11") (pinfunction "AVDD_11") (pintype "power_in"))
      (node (ref "IC13") (pin "19") (pinfunction "AVDD_19") (pintype "power_in"))
      (node (ref "IC13") (pin "23") (pinfunction "AVDD_23") (pintype "power_in"))
      (node (ref "IC13") (pin "24") (pinfunction "AVDD_24") (pintype "power_in"))
      (node (ref "L17") (pin "1") (pinfunction "1_1") (pintype "passive"))
    )
    (net (code "20") (name "/P1V8_CLK_VDD") (class "Default")
      (node (ref "C107") (pin "1") (pinfunction "1_1") (pintype "passive"))
      (node (ref "C112") (pin "1") (pinfunction "1_1") (pintype "passive"))
      (node (ref "C115") (pin "1") (pinfunction "1_1") (pintype "passive"))
      (node (ref "C116") (pin "2") (pinfunction "2_2") (pintype "passive"))
      (node (ref "C117") (pin "2") (pinfunction "2_2") (pintype "passive"))
      (node (ref "C118") (pin "2") (pinfunction "2_2") (pintype "passive"))
      (node (ref "C119") (pin "2") (pinfunction "2_2") (pintype "passive"))
      (node (ref "C120") (pin "2") (pinfunction "2_2") (pintype "passive"))
      (node (ref "C127") (pin "2") (pinfunction "2_2") (pintype "passive"))
      (node (ref "C128") (pin "2") (pinfunction "2_2") (pintype "passive"))
      (node (ref "C133") (pin "2") (pinfunction "2_2") (pintype "passive"))
      (node (ref "C134") (pin "2") (pinfunction "2_2") (pintype "passive"))
      (node (ref "C30") (pin "1") (pinfunction "1_1") (pintype "passive"))
      (node (ref "C44") (pin "1") (pinfunction "1_1") (pintype "passive"))
      (node (ref "C72") (pin "1") (pinfunction "1_1") (pintype "passive"))
      (node (ref "C99") (pin "1") (pinfunction "1_1") (pintype "passive"))
      (node (ref "IC13") (pin "25") (pinfunction "AVDD_25") (pintype "power_in"))
      (node (ref "IC13") (pin "26") (pinfunction "AVDD_26") (pintype "power_in"))
      (node (ref "IC13") (pin "29") (pinfunction "AVDD_29") (pintype "power_in"))
      (node (ref "IC13") (pin "30") (pinfunction "AVDD_30") (pintype "power_in"))
      (node (ref "IC2") (pin "3") (pinfunction "AVDD_(1.8V)_3") (pintype "power_in"))
      (node (ref "IC2") (pin "6") (pinfunction "AVDD_(1.8V)_6") (pintype "power_in"))
      (node (ref "IC2") (pin "89") (pinfunction "AVDD_(1.8V)_89") (pintype "power_in"))
      (node (ref "IC2") (pin "92") (pinfunction "AVDD_(1.8V)_92") (pintype "power_in"))
      (node (ref "L16") (pin "1") (pinfunction "1_1") (pintype "passive"))
    )
    (net (code "21") (name "/P1V8_DACCLK") (class "Default")
      (node (ref "C143") (pin "2") (pinfunction "2_2") (pintype "passive"))
      (node (ref "C144") (pin "2") (pinfunction "2_2") (pintype "passive"))
      (node (ref "IC13") (pin "44") (pinfunction "AVDD_44") (pintype "power_in"))
      (node (ref "IC13") (pin "45") (pinfunction "AVDD_45") (pintype "power_in"))
      (node (ref "L19") (pin "1") (pinfunction "1_1") (pintype "passive"))
    )
    (net (code "22") (name "/P1V8_DACDEC") (class "Default")
      (node (ref "C149") (pin "2") (pinfunction "2_2") (pintype "passive"))
      (node (ref "C150") (pin "2") (pinfunction "2_2") (pintype "passive"))
      (node (ref "IC13") (pin "53") (pinfunction "AVDD_53") (pintype "power_in"))
      (node (ref "L21") (pin "1") (pinfunction "1_1") (pintype "passive"))
    )
    (net (code "23") (name "/P1V8_DRV") (class "Default")
      (node (ref "C146") (pin "2") (pinfunction "2_2") (pintype "passive"))
      (node (ref "C147") (pin "2") (pinfunction "2_2") (pintype "passive"))
      (node (ref "C148") (pin "2") (pinfunction "2_2") (pintype "passive"))
      (node (ref "IC13") (pin "36") (pinfunction "AVDD_36") (pintype "power_in"))
      (node (ref "IC13") (pin "42") (pinfunction "AVDD_42") (pintype "power_in"))
      (node (ref "L20") (pin "1") (pinfunction "1_1") (pintype "passive"))
      (node (ref "R93") (pin "2") (pinfunction "2_2") (pintype "passive"))
    )
    (net (code "24") (name "/P1V8_DVDD") (class "Default")
      (node (ref "C151") (pin "2") (pinfunction "2_2") (pintype "passive"))
      (node (ref "C153") (pin "2") (pinfunction "2_2") (pintype "passive"))
      (node (ref "C154") (pin "2") (pinfunction "2_2") (pintype "passive"))
      (node (ref "C43") (pin "2") (pinfunction "2_2") (pintype "passive"))
      (node (ref "C51") (pin "2") (pinfunction "2_2") (pintype "passive"))
      (node (ref "C52") (pin "2") (pinfunction "2_2") (pintype "passive"))
      (node (ref "C53") (pin "2") (pinfunction "2_2") (pintype "passive"))
      (node (ref "C82") (pin "2") (pinfunction "2_2") (pintype "passive"))
      (node (ref "C83") (pin "2") (pinfunction "2_2") (pintype "passive"))
      (node (ref "C84") (pin "1") (pinfunction "1_1") (pintype "passive"))
      (node (ref "IC13") (pin "3") (pinfunction "DVDD_3") (pintype "power_in"))
      (node (ref "IC13") (pin "5") (pinfunction "DVDD_5") (pintype "power_in"))
      (node (ref "IC13") (pin "7") (pinfunction "DVDD_7") (pintype "power_in"))
      (node (ref "IC2") (pin "17") (pinfunction "DVDD_(1.8V)_17") (pintype "power_in"))
      (node (ref "IC2") (pin "23") (pinfunction "DVDD_(1.8V)_23") (pintype "power_in"))
      (node (ref "IC2") (pin "30") (pinfunction "DVDD_(1.8V)_30") (pintype "power_in"))
      (node (ref "IC2") (pin "47") (pinfunction "DVDD_(1.8V)_47") (pintype "power_in"))
      (node (ref "IC2") (pin "57") (pinfunction "DVDD_(1.8V)_57") (pintype "power_in"))
      (node (ref "IC2") (pin "64") (pinfunction "DVDD_(1.8V)_64") (pintype "power_in"))
      (node (ref "L22") (pin "1") (pinfunction "1_1") (pintype "passive"))
    )
    (net (code "25") (name "/P3V3_DAC") (class "Default")
      (node (ref "C124") (pin "2") (pinfunction "2_2") (pintype "passive"))
      (node (ref "C125") (pin "2") (pinfunction "2_2") (pintype "passive"))
      (node (ref "C126") (pin "2") (pinfunction "2_2") (pintype "passive"))
      (node (ref "C129") (pin "2") (pinfunction "2_2") (pintype "passive"))
      (node (ref "C130") (pin "2") (pinfunction "2_2") (pintype "passive"))
      (node (ref "C157") (pin "2") (pinfunction "2_2") (pintype "passive"))
      (node (ref "C158") (pin "2") (pinfunction "2_2") (pintype "passive"))
      (node (ref "C159") (pin "2") (pinfunction "2_2") (pintype "passive"))
      (node (ref "C162") (pin "1") (pinfunction "1_1") (pintype "passive"))
      (node (ref "IC13") (pin "46") (pinfunction "AVDD3_46") (pintype "power_in"))
      (node (ref "IC13") (pin "47") (pinfunction "AVDD3_47") (pintype "power_in"))
      (node (ref "IC13") (pin "49") (pinfunction "AVDD3_49") (pintype "power_in"))
      (node (ref "IC2") (pin "74") (pinfunction "AVDD_(3.3V)_74") (pintype "power_in"))
      (node (ref "IC2") (pin "75") (pinfunction "AVDD_(3.3V)_75") (pintype "power_in"))
      (node (ref "IC2") (pin "76") (pinfunction "AVDD_(3.3V)_76") (pintype "power_in"))
      (node (ref "IC2") (pin "77") (pinfunction "AVDD_(3.3V)_77") (pintype "power_in"))
      (node (ref "IC2") (pin "83") (pinfunction "AVDD_(3.3V)_83") (pintype "power_in"))
      (node (ref "L15") (pin "1") (pinfunction "1_1") (pintype "passive"))
      (node (ref "R96") (pin "2") (pinfunction "2_2") (pintype "passive"))
      (node (ref "R97") (pin "2") (pinfunction "2_2") (pintype "passive"))
      (node (ref "R98") (pin "2") (pinfunction "2_2") (pintype "passive"))
      (node (ref "R99") (pin "2") (pinfunction "2_2") (pintype "passive"))
    )
    (net (code "26") (name "/P3V3_DRV") (class "Default")
      (node (ref "C105") (pin "2") (pinfunction "2_2") (pintype "passive"))
      (node (ref "C106") (pin "2") (pinfunction "2_2") (pintype "passive"))
      (node (ref "C108") (pin "2") (pinfunction "2_2") (pintype "passive"))
      (node (ref "C109") (pin "2") (pinfunction "2_2") (pintype "passive"))
      (node (ref "C110") (pin "2") (pinfunction "2_2") (pintype "passive"))
      (node (ref "C111") (pin "2") (pinfunction "2_2") (pintype "passive"))
      (node (ref "C114") (pin "1") (pinfunction "1_1") (pintype "passive"))
      (node (ref "C137") (pin "2") (pinfunction "2_2") (pintype "passive"))
      (node (ref "C141") (pin "2") (pinfunction "2_2") (pintype "passive"))
      (node (ref "C142") (pin "2") (pinfunction "2_2") (pintype "passive"))
      (node (ref "C85") (pin "2") (pinfunction "2_2") (pintype "passive"))
      (node (ref "IC13") (pin "1") (pinfunction "DVDD_I/O_1") (pintype "power_in"))
      (node (ref "IC13") (pin "14") (pinfunction "AVDD3_14") (pintype "power_in"))
      (node (ref "IC13") (pin "37") (pinfunction "AVDD3_37") (pintype "power_in"))
      (node (ref "IC2") (pin "11") (pinfunction "DVDD_I/O_(3.3V)_11") (pintype "power_in"))
      (node (ref "IC2") (pin "15") (pinfunction "DVDD_I/O_(3.3V)_15") (pintype "power_in"))
      (node (ref "IC2") (pin "21") (pinfunction "DVDD_I/O_(3.3V)_21") (pintype "power_in"))
      (node (ref "IC2") (pin "28") (pinfunction "DVDD_I/O_(3.3V)_28") (pintype "power_in"))
      (node (ref "IC2") (pin "45") (pinfunction "DVDD_I/O_(3.3V)_45") (pintype "power_in"))
      (node (ref "IC2") (pin "56") (pinfunction "DVDD_I/O_(3.3V)_56") (pintype "power_in"))
      (node (ref "IC2") (pin "66") (pinfunction "DVDD_I/O_(3.3V)_66") (pintype "power_in"))
      (node (ref "L18") (pin "1") (pinfunction "1_1") (pintype "passive"))
    )
    (net (code "27") (name "/PLL_LOCK") (class "Default")
      (node (ref "IC2") (pin "19") (pinfunction "PLL_LOCK_19") (pintype "output+no_connect"))
    )
    (net (code "28") (name "/RAMP_CTL.DRCTL") (class "Default")
      (node (ref "IC2") (pin "62") (pinfunction "DRCTL_62") (pintype "input"))
    )
    (net (code "29") (name "/RAMP_CTL.DRHOLD") (class "Default")
      (node (ref "IC2") (pin "63") (pinfunction "DRHOLD_63") (pintype "input"))
    )
    (net (code "30") (name "/RAMP_CTL.DROVER") (class "Default")
      (node (ref "IC2") (pin "61") (pinfunction "DROVER_61") (pintype "output+no_connect"))
    )
    (net (code "31") (name "/RESET") (class "Default")
      (node (ref "IC13") (pin "59") (pinfunction "RESET_59") (pintype "input"))
    )
    (net (code "32") (name "/RSET") (class "Default")
      (node (ref "IC13") (pin "48") (pinfunction "DAC_RSET_48") (pintype "output"))
      (node (ref "R15") (pin "1") (pinfunction "1_1") (pintype "passive"))
    )
    (net (code "33") (name "/RSET1") (class "Default")
      (node (ref "IC2") (pin "84") (pinfunction "DAC_RSET_84") (pintype "output"))
      (node (ref "R112") (pin "1") (pinfunction "1_1") (pintype "passive"))
    )
    (net (code "34") (name "/S1") (class "Default")
      (node (ref "IC13") (pin "9") (pinfunction "S1_9") (pintype "bidirectional"))
      (node (ref "R104") (pin "2") (pinfunction "2_2") (pintype "passive"))
      (node (ref "R96") (pin "1") (pinfunction "1_1") (pintype "passive"))
    )
    (net (code "35") (name "/S2") (class "Default")
      (node (ref "IC13") (pin "10") (pinfunction "S2_10") (pintype "bidirectional"))
      (node (ref "R105") (pin "2") (pinfunction "2_2") (pintype "passive"))
      (node (ref "R97") (pin "1") (pinfunction "1_1") (pintype "passive"))
    )
    (net (code "36") (name "/S3") (class "Default")
      (node (ref "IC13") (pin "54") (pinfunction "S3_54") (pintype "bidirectional"))
      (node (ref "R106") (pin "2") (pinfunction "2_2") (pintype "passive"))
      (node (ref "R98") (pin "1") (pinfunction "1_1") (pintype "passive"))
    )
    (net (code "37") (name "/S4") (class "Default")
      (node (ref "IC13") (pin "55") (pinfunction "S4_55") (pintype "bidirectional"))
      (node (ref "R107") (pin "2") (pinfunction "2_2") (pintype "passive"))
      (node (ref "R99") (pin "1") (pinfunction "1_1") (pintype "passive"))
    )
    (net (code "38") (name "/SCKI") (class "Default")
      (node (ref "IC13") (pin "64") (pinfunction "SCLK_64") (pintype "input"))
      (node (ref "IC2") (pin "69") (pinfunction "SCLK_69") (pintype "input"))
      (node (ref "R40") (pin "2") (pinfunction "2_2") (pintype "passive"))
    )
    (net (code "39") (name "/SDI") (class "Default")
      (node (ref "IC13") (pin "63") (pinfunction "SDIO_63") (pintype "bidirectional"))
      (node (ref "IC2") (pin "67") (pinfunction "SDIO_67") (pintype "bidirectional"))
      (node (ref "R41") (pin "2") (pinfunction "2_2") (pintype "passive"))
    )
    (net (code "40") (name "/SDO") (class "Default")
      (node (ref "IC13") (pin "62") (pinfunction "SDO_62") (pintype "output"))
      (node (ref "IC2") (pin "68") (pinfunction "SDO_68") (pintype "output"))
    )
    (net (code "41") (name "/SYNC_CLK") (class "Default")
      (node (ref "IC2") (pin "55") (pinfunction "SYNC_CLK_55") (pintype "output+no_connect"))
    )
    (net (code "42") (name "/SYNC_IN_N") (class "Default")
      (node (ref "IC2") (pin "8") (pinfunction "SYNC_IN-_8") (pintype "input"))
    )
    (net (code "43") (name "/SYNC_IN_P") (class "Default")
      (node (ref "IC2") (pin "7") (pinfunction "SYNC_IN+_7") (pintype "input"))
    )
    (net (code "44") (name "/SYNC_OUT_N") (class "Default")
      (node (ref "IC2") (pin "10") (pinfunction "SYNC_OUT-_10") (pintype "output"))
    )
    (net (code "45") (name "/SYNC_OUT_P") (class "Default")
      (node (ref "IC2") (pin "9") (pinfunction "SYNC_OUT+_9") (pintype "output"))
    )
    (net (code "46") (name "/SYNC_SMP_ERR") (class "Default")
      (node (ref "IC2") (pin "12") (pinfunction "SYNC_SMP_ERR_12") (pintype "output+no_connect"))
    )
    (net (code "47") (name "GND") (class "Default")
      (node (ref "C105") (pin "1") (pinfunction "1_1") (pintype "passive"))
      (node (ref "C106") (pin "1") (pinfunction "1_1") (pintype "passive"))
      (node (ref "C108") (pin "1") (pinfunction "1_1") (pintype "passive"))
      (node (ref "C109") (pin "1") (pinfunction "1_1") (pintype "passive"))
      (node (ref "C110") (pin "1") (pinfunction "1_1") (pintype "passive"))
      (node (ref "C111") (pin "1") (pinfunction "1_1") (pintype "passive"))
      (node (ref "C114") (pin "2") (pinfunction "2_2") (pintype "passive"))
      (node (ref "C115") (pin "2") (pinfunction "2_2") (pintype "passive"))
      (node (ref "C116") (pin "1") (pinfunction "1_1") (pintype "passive"))
      (node (ref "C117") (pin "1") (pinfunction "1_1") (pintype "passive"))
      (node (ref "C118") (pin "1") (pinfunction "1_1") (pintype "passive"))
      (node (ref "C119") (pin "1") (pinfunction "1_1") (pintype "passive"))
      (node (ref "C120") (pin "1") (pinfunction "1_1") (pintype "passive"))
      (node (ref "C124") (pin "1") (pinfunction "1_1") (pintype "passive"))
      (node (ref "C125") (pin "1") (pinfunction "1_1") (pintype "passive"))
      (node (ref "C126") (pin "1") (pinfunction "1_1") (pintype "passive"))
      (node (ref "C127") (pin "1") (pinfunction "1_1") (pintype "passive"))
      (node (ref "C128") (pin "1") (pinfunction "1_1") (pintype "passive"))
      (node (ref "C129") (pin "1") (pinfunction "1_1") (pintype "passive"))
      (node (ref "C130") (pin "1") (pinfunction "1_1") (pintype "passive"))
      (node (ref "C133") (pin "1") (pinfunction "1_1") (pintype "passive"))
      (node (ref "C134") (pin "1") (pinfunction "1_1") (pintype "passive"))
      (node (ref "C135") (pin "1") (pinfunction "1_1") (pintype "passive"))
      (node (ref "C136") (pin "1") (pinfunction "1_1") (pintype "passive"))
      (node (ref "C137") (pin "1") (pinfunction "1_1") (pintype "passive"))
      (node (ref "C138") (pin "1") (pinfunction "1_1") (pintype "passive"))
      (node (ref "C140") (pin "1") (pinfunction "1_1") (pintype "passive"))
      (node (ref "C141") (pin "1") (pinfunction "1_1") (pintype "passive"))
      (node (ref "C142") (pin "1") (pinfunction "1_1") (pintype "passive"))
      (node (ref "C143") (pin "1") (pinfunction "1_1") (pintype "passive"))
      (node (ref "C144") (pin "1") (pinfunction "1_1") (pintype "passive"))
      (node (ref "C146") (pin "1") (pinfunction "1_1") (pintype "passive"))
      (node (ref "C147") (pin "1") (pinfunction "1_1") (pintype "passive"))
      (node (ref "C148") (pin "1") (pinfunction "1_1") (pintype "passive"))
      (node (ref "C149") (pin "1") (pinfunction "1_1") (pintype "passive"))
      (node (ref "C150") (pin "1") (pinfunction "1_1") (pintype "passive"))
      (node (ref "C151") (pin "1") (pinfunction "1_1") (pintype "passive"))
      (node (ref "C153") (pin "1") (pinfunction "1_1") (pintype "passive"))
      (node (ref "C154") (pin "1") (pinfunction "1_1") (pintype "passive"))
      (node (ref "C157") (pin "1") (pinfunction "1_1") (pintype "passive"))
      (node (ref "C158") (pin "1") (pinfunction "1_1") (pintype "passive"))
      (node (ref "C159") (pin "1") (pinfunction "1_1") (pintype "passive"))
      (node (ref "C162") (pin "2") (pinfunction "2_2") (pintype "passive"))
      (node (ref "C26") (pin "1") (pinfunction "1_1") (pintype "passive"))
      (node (ref "C43") (pin "1") (pinfunction "1_1") (pintype "passive"))
      (node (ref "C51") (pin "1") (pinfunction "1_1") (pintype "passive"))
      (node (ref "C52") (pin "1") (pinfunction "1_1") (pintype "passive"))
      (node (ref "C53") (pin "1") (pinfunction "1_1") (pintype "passive"))
      (node (ref "C82") (pin "1") (pinfunction "1_1") (pintype "passive"))
      (node (ref "C83") (pin "1") (pinfunction "1_1") (pintype "passive"))
      (node (ref "C84") (pin "2") (pinfunction "2_2") (pintype "passive"))
      (node (ref "C85") (pin "1") (pinfunction "1_1") (pintype "passive"))
      (node (ref "C87") (pin "1") (pinfunction "1_1") (pintype "passive"))
      (node (ref "IC13") (pin "2") (pinfunction "DVSS_2") (pintype "power_in"))
      (node (ref "IC13") (pin "33") (pinfunction "AVSS_33") (pintype "power_in"))
      (node (ref "IC13") (pin "39") (pinfunction "AVSS_39") (pintype "power_in"))
      (node (ref "IC13") (pin "4") (pinfunction "DVSS_4") (pintype "power_in"))
      (node (ref "IC13") (pin "43") (pinfunction "AVSS_43") (pintype "power_in"))
      (node (ref "IC13") (pin "52") (pinfunction "AVSS_52") (pintype "power_in"))
      (node (ref "IC13") (pin "56") (pinfunction "DVSS_56") (pintype "power_in"))
      (node (ref "IC13") (pin "57") (pinfunction "DVSS_57") (pintype "power_in"))
      (node (ref "IC13") (pin "58") (pinfunction "PWRDOWN_58") (pintype "input"))
      (node (ref "IC13") (pin "6") (pinfunction "DVSS_6") (pintype "power_in"))
      (node (ref "IC13") (pin "65") (pinfunction "EP_65") (pintype "power_in"))
      (node (ref "IC13") (pin "8") (pinfunction "DVSS_8") (pintype "power_in"))
      (node (ref "IC2") (pin "101") (pinfunction "EP(GND)_101") (pintype "power_in"))
      (node (ref "IC2") (pin "13") (pinfunction "DGND_13") (pintype "power_in"))
      (node (ref "IC2") (pin "16") (pinfunction "DGND_16") (pintype "power_in"))
      (node (ref "IC2") (pin "18") (pinfunction "EXT_PWR_DWN_18") (pintype "input"))
      (node (ref "IC2") (pin "22") (pinfunction "DGND_22") (pintype "power_in"))
      (node (ref "IC2") (pin "25") (pinfunction "D15_25") (pintype "input"))
      (node (ref "IC2") (pin "26") (pinfunction "D14_26") (pintype "input"))
      (node (ref "IC2") (pin "27") (pinfunction "D13_27") (pintype "input"))
      (node (ref "IC2") (pin "29") (pinfunction "DGND_29") (pintype "power_in"))
      (node (ref "IC2") (pin "31") (pinfunction "D12_31") (pintype "input"))
      (node (ref "IC2") (pin "32") (pinfunction "D11_32") (pintype "input"))
      (node (ref "IC2") (pin "33") (pinfunction "D10_33") (pintype "input"))
      (node (ref "IC2") (pin "34") (pinfunction "D9_34") (pintype "input"))
      (node (ref "IC2") (pin "35") (pinfunction "D8_35") (pintype "input"))
      (node (ref "IC2") (pin "36") (pinfunction "D7_36") (pintype "input"))
      (node (ref "IC2") (pin "37") (pinfunction "D6_37") (pintype "input"))
      (node (ref "IC2") (pin "38") (pinfunction "D5_38") (pintype "input"))
      (node (ref "IC2") (pin "39") (pinfunction "D4_39") (pintype "input"))
      (node (ref "IC2") (pin "4") (pinfunction "AGND_4") (pintype "power_in"))
      (node (ref "IC2") (pin "41") (pinfunction "TxENABLE_41") (pintype "input"))
      (node (ref "IC2") (pin "42") (pinfunction "D3_42") (pintype "input"))
      (node (ref "IC2") (pin "43") (pinfunction "D2_43") (pintype "input"))
      (node (ref "IC2") (pin "44") (pinfunction "D1_44") (pintype "input"))
      (node (ref "IC2") (pin "46") (pinfunction "DGND_46") (pintype "power_in"))
      (node (ref "IC2") (pin "48") (pinfunction "D0_48") (pintype "input"))
      (node (ref "IC2") (pin "49") (pinfunction "F1_49") (pintype "input"))
      (node (ref "IC2") (pin "5") (pinfunction "AGND_5") (pintype "power_in"))
      (node (ref "IC2") (pin "50") (pinfunction "F0_50") (pintype "input"))
      (node (ref "IC2") (pin "51") (pinfunction "DGND_51") (pintype "power_in"))
      (node (ref "IC2") (pin "58") (pinfunction "DGND_58") (pintype "power_in"))
      (node (ref "IC2") (pin "65") (pinfunction "DGND_65") (pintype "power_in"))
      (node (ref "IC2") (pin "73") (pinfunction "AGND_73") (pintype "power_in"))
      (node (ref "IC2") (pin "78") (pinfunction "AGND_78") (pintype "power_in"))
      (node (ref "IC2") (pin "79") (pinfunction "AGND_79") (pintype "power_in"))
      (node (ref "IC2") (pin "82") (pinfunction "AGND_82") (pintype "power_in"))
      (node (ref "IC2") (pin "85") (pinfunction "AGND_85") (pintype "power_in"))
      (node (ref "IC2") (pin "88") (pinfunction "AGND_88") (pintype "power_in"))
      (node (ref "IC2") (pin "96") (pinfunction "AGND_96") (pintype "power_in"))
      (node (ref "R104") (pin "1") (pinfunction "1_1") (pintype "passive"))
      (node (ref "R105") (pin "1") (pinfunction "1_1") (pintype "passive"))
      (node (ref "R106") (pin "1") (pinfunction "1_1") (pintype "passive"))
      (node (ref "R107") (pin "1") (pinfunction "1_1") (pintype "passive"))
      (node (ref "R112") (pin "2") (pinfunction "2_2") (pintype "passive"))
      (node (ref "R15") (pin "2") (pinfunction "2_2") (pintype "passive"))
      (node (ref "R88") (pin "1") (pinfunction "1_1") (pintype "passive"))
      (node (ref "R89") (pin "2") (pinfunction "2_2") (pintype "passive"))
      (node (ref "R94") (pin "1") (pinfunction "1_1") (pintype "passive"))
    )
    (net (code "48") (name "Net-(C26-Pad2)") (class "Default")
      (node (ref "C26") (pin "2") (pinfunction "2_2") (pintype "passive"))
      (node (ref "R41") (pin "1") (pinfunction "1_1") (pintype "passive"))
    )
    (net (code "49") (name "Net-(C72-Pad2)") (class "Default")
      (node (ref "C72") (pin "2") (pinfunction "2_2") (pintype "passive"))
      (node (ref "C99") (pin "2") (pinfunction "2_2") (pintype "passive"))
      (node (ref "R92") (pin "1") (pinfunction "1_1") (pintype "passive"))
    )
    (net (code "50") (name "Net-(C87-Pad2)") (class "Default")
      (node (ref "C87") (pin "2") (pinfunction "2_2") (pintype "passive"))
      (node (ref "R40") (pin "1") (pinfunction "1_1") (pintype "passive"))
    )
    (net (code "51") (name "Net-(C107-Pad2)") (class "Default")
      (node (ref "C107") (pin "2") (pinfunction "2_2") (pintype "passive"))
      (node (ref "C44") (pin "2") (pinfunction "2_2") (pintype "passive"))
      (node (ref "R113") (pin "1") (pinfunction "1_1") (pintype "passive"))
    )
    (net (code "52") (name "Net-(IC2-IOUT-Pad80)") (class "Default")
      (node (ref "IC2") (pin "80") (pinfunction "IOUT_80") (pintype "output"))
      (node (ref "R56") (pin "1") (pinfunction "1_1") (pintype "passive"))
    )
    (net (code "53") (name "Net-(IC2-IOUT-Pad81)") (class "Default")
      (node (ref "IC2") (pin "81") (pinfunction "IOUT_81") (pintype "output"))
      (node (ref "R78") (pin "1") (pinfunction "1_1") (pintype "passive"))
    )
    (net (code "54") (name "Net-(IC2-XTAL_SEL)") (class "Default")
      (node (ref "IC2") (pin "95") (pinfunction "XTAL_SEL_95") (pintype "input"))
      (node (ref "R88") (pin "2") (pinfunction "2_2") (pintype "passive"))
    )
    (net (code "55") (name "Net-(IC13-CLKMODESEL)") (class "Default")
      (node (ref "IC13") (pin "32") (pinfunction "CLKMODESEL_32") (pintype "input"))
      (node (ref "R93") (pin "1") (pinfunction "1_1") (pintype "passive"))
      (node (ref "R94") (pin "2") (pinfunction "2_2") (pintype "passive"))
    )
    (net (code "56") (name "Net-(R90-Pad1)") (class "Default")
      (node (ref "R90") (pin "1") (pinfunction "1_1") (pintype "passive"))
      (node (ref "R92") (pin "2") (pinfunction "2_2") (pintype "passive"))
    )
    (net (code "57") (name "Net-(R113-Pad2)") (class "Default")
      (node (ref "R113") (pin "2") (pinfunction "2_2") (pintype "passive"))
      (node (ref "R140") (pin "1") (pinfunction "1_1") (pintype "passive"))
    )
    (net (code "58") (name "P1V8A") (class "Default")
      (node (ref "L16") (pin "2") (pinfunction "2_2") (pintype "passive"))
      (node (ref "L17") (pin "2") (pinfunction "2_2") (pintype "passive"))
      (node (ref "L19") (pin "2") (pinfunction "2_2") (pintype "passive"))
      (node (ref "L20") (pin "2") (pinfunction "2_2") (pintype "passive"))
      (node (ref "L21") (pin "2") (pinfunction "2_2") (pintype "passive"))
      (node (ref "L22") (pin "2") (pinfunction "2_2") (pintype "passive"))
    )
    (net (code "59") (name "P3V3A") (class "Default")
      (node (ref "L15") (pin "2") (pinfunction "2_2") (pintype "passive"))
      (node (ref "L18") (pin "2") (pinfunction "2_2") (pintype "passive"))
    )
    (net (code "60") (name "unconnected-(IC2-NC-Pad1)") (class "Default")
      (node (ref "IC2") (pin "1") (pinfunction "NC_1") (pintype "passive+no_connect"))
    )
    (net (code "61") (name "unconnected-(IC2-NC-Pad20)") (class "Default")
      (node (ref "IC2") (pin "20") (pinfunction "NC_20") (pintype "passive+no_connect"))
    )
    (net (code "62") (name "unconnected-(IC2-NC-Pad72)") (class "Default")
      (node (ref "IC2") (pin "72") (pinfunction "NC_72") (pintype "passive+no_connect"))
    )
    (net (code "63") (name "unconnected-(IC2-NC-Pad86)") (class "Default")
      (node (ref "IC2") (pin "86") (pinfunction "NC_86") (pintype "passive+no_connect"))
    )
    (net (code "64") (name "unconnected-(IC2-NC-Pad87)") (class "Default")
      (node (ref "IC2") (pin "87") (pinfunction "NC_87") (pintype "passive+no_connect"))
    )
    (net (code "65") (name "unconnected-(IC2-NC-Pad93)") (class "Default")
      (node (ref "IC2") (pin "93") (pinfunction "NC_93") (pintype "passive+no_connect"))
    )
    (net (code "66") (name "unconnected-(IC2-NC-Pad97)") (class "Default")
      (node (ref "IC2") (pin "97") (pinfunction "NC_97") (pintype "passive+no_connect"))
    )
    (net (code "67") (name "unconnected-(IC2-NC-Pad98)") (class "Default")
      (node (ref "IC2") (pin "98") (pinfunction "NC_98") (pintype "passive+no_connect"))
    )
    (net (code "68") (name "unconnected-(IC2-NC-Pad99)") (class "Default")
      (node (ref "IC2") (pin "99") (pinfunction "NC_99") (pintype "passive+no_connect"))
    )
    (net (code "69") (name "unconnected-(IC2-NC-Pad100)") (class "Default")
      (node (ref "IC2") (pin "100") (pinfunction "NC_100") (pintype "passive+no_connect"))
    )
    (net (code "70") (name "unconnected-(IC2-PDCLK-Pad40)") (class "Default")
      (node (ref "IC2") (pin "40") (pinfunction "PDCLK_40") (pintype "output+no_connect"))
    )
    (net (code "71") (name "unconnected-(IC2-RAM_SWP_OVR-Pad24)") (class "Default")
      (node (ref "IC2") (pin "24") (pinfunction "RAM_SWP_OVR_24") (pintype "output+no_connect"))
    )
    (net (code "72") (name "unconnected-(IC2-REFCLK_OUT-Pad94)") (class "Default")
      (node (ref "IC2") (pin "94") (pinfunction "REFCLK_OUT_94") (pintype "output+no_connect"))
    )
    (net (code "73") (name "unconnected-(IC13-FDBK_IN-Pad41)") (class "Default")
      (node (ref "IC13") (pin "41") (pinfunction "FDBK_IN_41") (pintype "input+no_connect"))
    )
    (net (code "74") (name "unconnected-(IC13-FDBK_INB-Pad40)") (class "Default")
      (node (ref "IC13") (pin "40") (pinfunction "FDBK_INB_40") (pintype "input+no_connect"))
    )
    (net (code "75") (name "unconnected-(IC13-NC-Pad12)") (class "Default")
      (node (ref "IC13") (pin "12") (pinfunction "NC_12") (pintype "passive+no_connect"))
    )
    (net (code "76") (name "unconnected-(IC13-NC-Pad13)") (class "Default")
      (node (ref "IC13") (pin "13") (pinfunction "NC_13") (pintype "passive+no_connect"))
    )
    (net (code "77") (name "unconnected-(IC13-NC-Pad15)") (class "Default")
      (node (ref "IC13") (pin "15") (pinfunction "NC_15") (pintype "passive+no_connect"))
    )
    (net (code "78") (name "unconnected-(IC13-NC-Pad16)") (class "Default")
      (node (ref "IC13") (pin "16") (pinfunction "NC_16") (pintype "passive+no_connect"))
    )
    (net (code "79") (name "unconnected-(IC13-NC-Pad17)") (class "Default")
      (node (ref "IC13") (pin "17") (pinfunction "NC_17") (pintype "passive+no_connect"))
    )
    (net (code "80") (name "unconnected-(IC13-NC-Pad18)") (class "Default")
      (node (ref "IC13") (pin "18") (pinfunction "NC_18") (pintype "passive+no_connect"))
    )
    (net (code "81") (name "unconnected-(IC13-NC-Pad20)") (class "Default")
      (node (ref "IC13") (pin "20") (pinfunction "NC_20") (pintype "passive+no_connect"))
    )
    (net (code "82") (name "unconnected-(IC13-NC-Pad21)") (class "Default")
      (node (ref "IC13") (pin "21") (pinfunction "NC_21") (pintype "passive+no_connect"))
    )
    (net (code "83") (name "unconnected-(IC13-NC-Pad22)") (class "Default")
      (node (ref "IC13") (pin "22") (pinfunction "NC_22") (pintype "passive+no_connect"))
    )
    (net (code "84") (name "unconnected-(IC13-OUT-Pad35)") (class "Default")
      (node (ref "IC13") (pin "35") (pinfunction "OUT_35") (pintype "output+no_connect"))
    )
    (net (code "85") (name "unconnected-(IC13-OUTB-Pad34)") (class "Default")
      (node (ref "IC13") (pin "34") (pinfunction "OUTB_34") (pintype "output+no_connect"))
    )
    (net (code "86") (name "unconnected-(IC13-OUT_CMOS-Pad38)") (class "Default")
      (node (ref "IC13") (pin "38") (pinfunction "OUT_CMOS_38") (pintype "output+no_connect"))
    )
  )
)
